# Sound_Intimator.net
KiCad netlist of a schematic drawn in Altium Designer
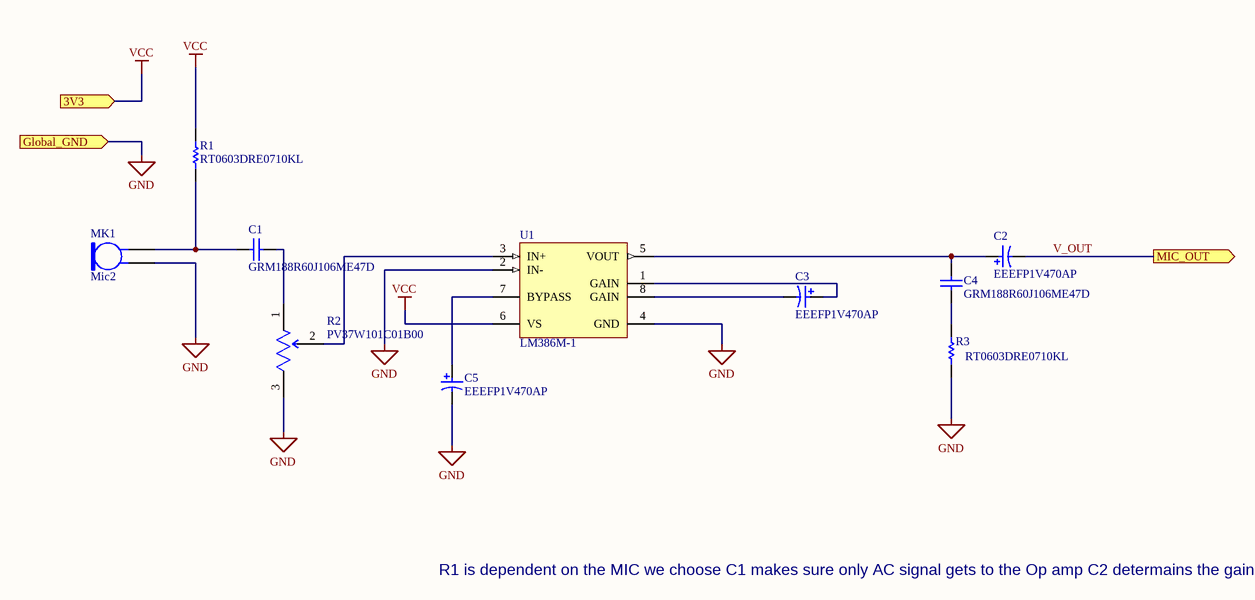
[diagram p0: Sound Intimator.SchDoc]

(export (version "E")
  (design (tool "Eeschema 10.0.6"))
  (components
    (comp (ref "C1")
      (value "GRM188R60J106ME47D")
      (footprint "CAPC1608X90X35NL10T15")
      (fields (field (name "MANUFACTURER") "Murata"))
      (libsource (lib "Altium Content Vault") (part "CAP"))
    )
    (comp (ref "C2")
      (value "EEEFP1V470AP")
      (footprint "PNSC-FP-V-D_V")
      (fields (field (name "MANUFACTURER") "Panasonic"))
      (libsource (lib "Altium Content Vault") (part "CAP-P-2"))
    )
    (comp (ref "C3")
      (value "EEEFP1V470AP")
      (footprint "PNSC-FP-V-D_V")
      (fields (field (name "MANUFACTURER") "Panasonic"))
      (libsource (lib "Altium Content Vault") (part "CAP-P-2"))
    )
    (comp (ref "C4")
      (value "GRM188R60J106ME47D")
      (footprint "CAPC1608X90X35NL10T15")
      (fields (field (name "MANUFACTURER") "Murata"))
      (libsource (lib "Altium Content Vault") (part "CAP"))
    )
    (comp (ref "C5")
      (value "EEEFP1V470AP")
      (footprint "PNSC-FP-V-D_V")
      (fields (field (name "MANUFACTURER") "Panasonic"))
      (libsource (lib "Altium Content Vault") (part "CAP-P-2"))
    )
    (comp (ref "MK1")
      (value "Mic2")
      (footprint "PIN2")
      (description "Microphone")
      (fields (field (name "PUBLISHER") "Altium Limited"))
      (libsource (lib "Miscellaneous Devices") (part "Mic2"))
    )
    (comp (ref "R1")
      (value "RT0603DRE0710KL")
      (footprint "RESC1608X55X25ML10T15")
      (fields (field (name "MANUFACTURER") "Yageo"))
      (libsource (lib "Altium Content Vault") (part "RES"))
    )
    (comp (ref "R2")
      (value "PV37W101C01B00")
      (footprint "FP-PV37W101C01B00-MFG")
      (description "TRIMMER 100 OHM 0.25W PC PIN TOP")
      (fields (field (name "TOLERANCE") "10%"))
      (libsource (lib "Altium Content Vault") (part "748d9263f5d5cb406a2c5b99dbcc035"))
    )
    (comp (ref "R3")
      (value "RT0603DRE0710KL")
      (footprint "RESC1608X55X25ML10T15")
      (fields (field (name "MANUFACTURER") "Yageo"))
      (libsource (lib "Altium Content Vault") (part "RES"))
    )
    (comp (ref "U1")
      (value "LM386M-1")
      (footprint "D0008A_M")
      (description "Low Voltage Audio Power Amplifier, 8-pin Narrow SOIC")
      (fields (field (name "MANUFACTURER") "Texas Instruments"))
      (libsource (lib "Altium Content Vault") (part "AMP-APA-LM386-8"))
    )
  )
  (nets
    (net (code "1") (name "/V_OUT") (class "Default")
      (node (ref "C2") (pin "2") (pinfunction "2_2") (pintype "passive"))
    )
    (net (code "2") (name "GND") (class "Default")
      (node (ref "C5") (pin "2") (pinfunction "2_2") (pintype "passive"))
      (node (ref "MK1") (pin "1") (pinfunction "1_1") (pintype "passive"))
      (node (ref "R2") (pin "3") (pinfunction "3_3") (pintype "passive"))
      (node (ref "R3") (pin "1") (pinfunction "1_1") (pintype "passive"))
      (node (ref "U1") (pin "2") (pinfunction "IN-_2") (pintype "input"))
      (node (ref "U1") (pin "4") (pinfunction "GND_4") (pintype "power_in"))
    )
    (net (code "3") (name "Net-(C1-Pad1)") (class "Default")
      (node (ref "C1") (pin "1") (pinfunction "1_1") (pintype "passive"))
      (node (ref "MK1") (pin "2") (pinfunction "2_2") (pintype "passive"))
      (node (ref "R1") (pin "1") (pinfunction "1_1") (pintype "passive"))
    )
    (net (code "4") (name "Net-(C1-Pad2)") (class "Default")
      (node (ref "C1") (pin "2") (pinfunction "2_2") (pintype "passive"))
      (node (ref "R2") (pin "1") (pinfunction "1_1") (pintype "passive"))
    )
    (net (code "5") (name "Net-(C3-Pad1)") (class "Default")
      (node (ref "C3") (pin "1") (pinfunction "1_1") (pintype "passive"))
      (node (ref "U1") (pin "1") (pinfunction "GAIN_1") (pintype "passive"))
    )
    (net (code "6") (name "Net-(C3-Pad2)") (class "Default")
      (node (ref "C3") (pin "2") (pinfunction "2_2") (pintype "passive"))
      (node (ref "U1") (pin "8") (pinfunction "GAIN_8") (pintype "passive"))
    )
    (net (code "7") (name "Net-(C4-Pad1)") (class "Default")
      (node (ref "C4") (pin "1") (pinfunction "1_1") (pintype "passive"))
      (node (ref "R3") (pin "2") (pinfunction "2_2") (pintype "passive"))
    )
    (net (code "8") (name "Net-(U1-BYPASS)") (class "Default")
      (node (ref "C5") (pin "1") (pinfunction "1_1") (pintype "passive"))
      (node (ref "U1") (pin "7") (pinfunction "BYPASS_7") (pintype "passive"))
    )
    (net (code "9") (name "Net-(U1-IN+)") (class "Default")
      (node (ref "R2") (pin "2") (pinfunction "2_2") (pintype "passive"))
      (node (ref "U1") (pin "3") (pinfunction "IN+_3") (pintype "input"))
    )
    (net (code "10") (name "Net-(U1-VOUT)") (class "Default")
      (node (ref "C2") (pin "1") (pinfunction "1_1") (pintype "passive"))
      (node (ref "C4") (pin "2") (pinfunction "2_2") (pintype "passive"))
      (node (ref "U1") (pin "5") (pinfunction "VOUT_5") (pintype "output"))
    )
    (net (code "11") (name "VCC") (class "Default")
      (node (ref "R1") (pin "2") (pinfunction "2_2") (pintype "passive"))
      (node (ref "U1") (pin "6") (pinfunction "VS_6") (pintype "power_in"))
    )
  )
)
